# main_7.net
KiCad netlist of a schematic drawn in Altium Designer
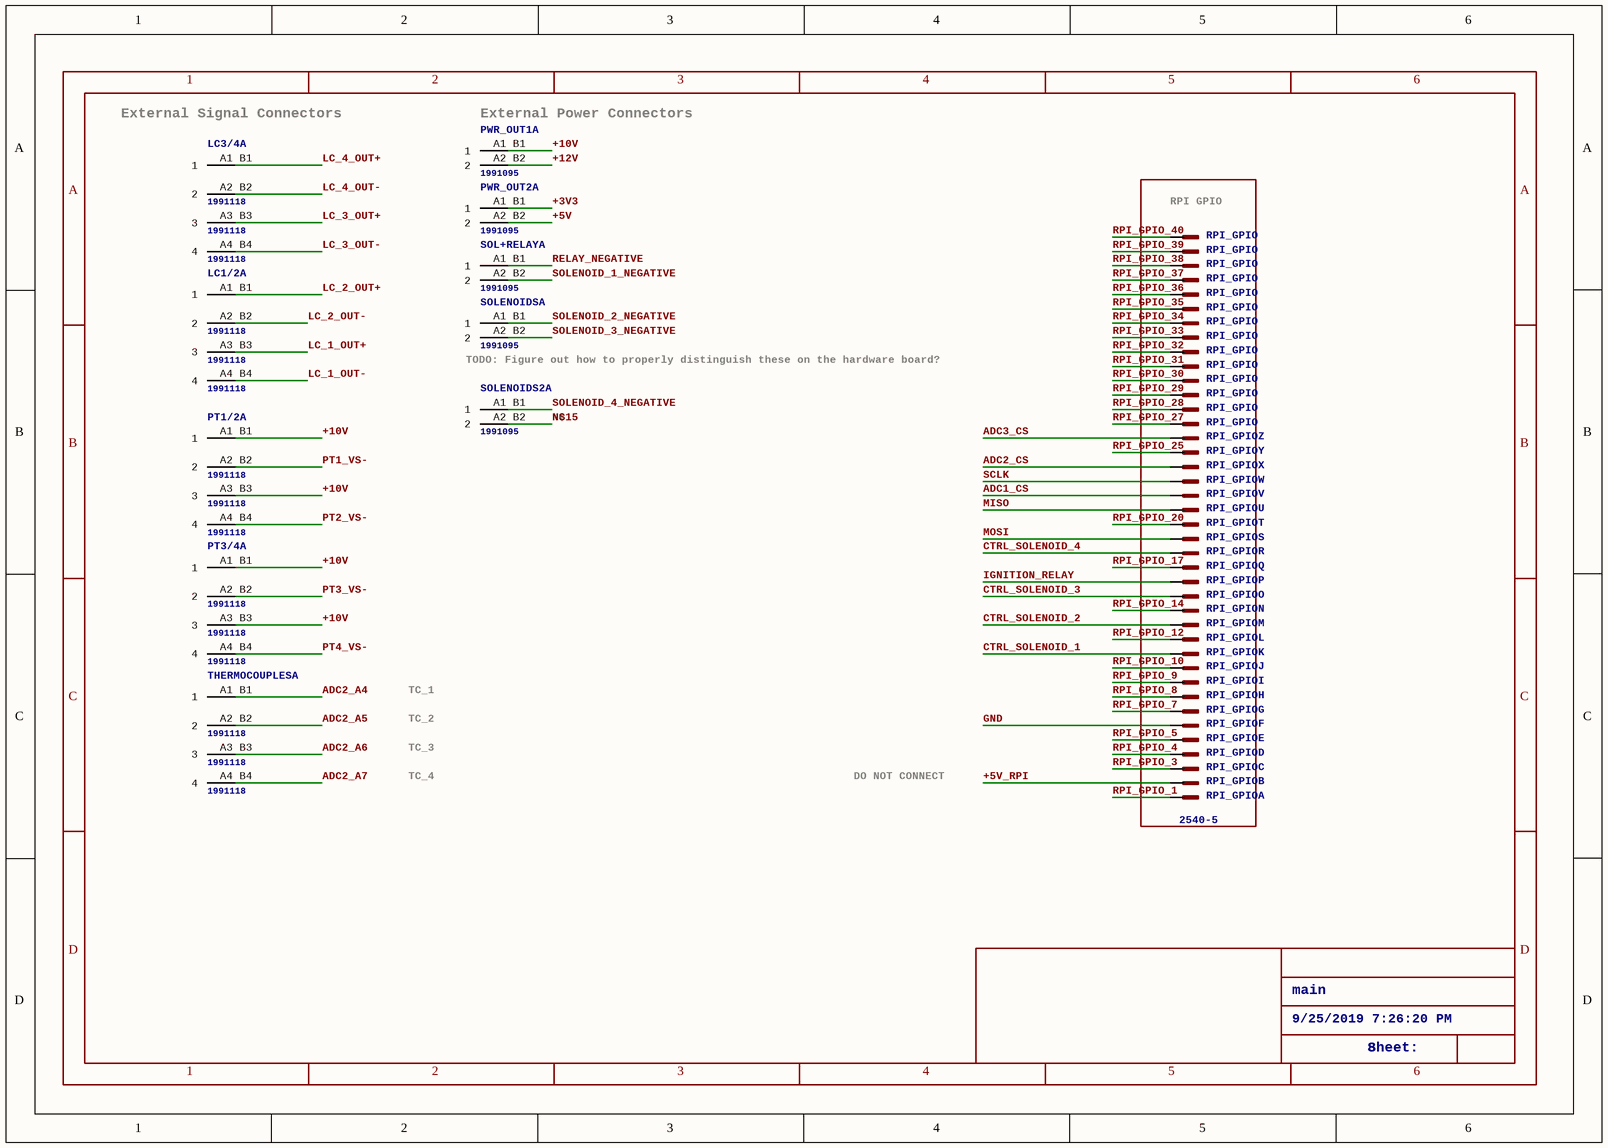
[diagram p0: main_7.SchDoc]

(export (version "E")
  (design (tool "Eeschema 10.0.6"))
  (components
    (comp (ref "LC1/2")
      (value "1991118")
      (footprint "1991118")
      (fields (field (name "LIBRARYNAME") "con-phoenix-500-extra"))
      (libsource (lib "con-phoenix-500-extra") (part "1991118"))
    )
    (comp (ref "LC3/4")
      (value "1991118")
      (footprint "1991118")
      (fields (field (name "LIBRARYNAME") "con-phoenix-500-extra"))
      (libsource (lib "con-phoenix-500-extra") (part "1991118"))
    )
    (comp (ref "PT1/2")
      (value "1991118")
      (footprint "1991118")
      (fields (field (name "LIBRARYNAME") "con-phoenix-500-extra"))
      (libsource (lib "con-phoenix-500-extra") (part "1991118"))
    )
    (comp (ref "PT3/4")
      (value "1991118")
      (footprint "1991118")
      (fields (field (name "LIBRARYNAME") "con-phoenix-500-extra"))
      (libsource (lib "con-phoenix-500-extra") (part "1991118"))
    )
    (comp (ref "PWR_OUT1")
      (value "1991095")
      (footprint "1991095")
      (fields (field (name "LIBRARYNAME") "con-phoenix-500-extra"))
      (libsource (lib "con-phoenix-500-extra") (part "1991095"))
    )
    (comp (ref "PWR_OUT2")
      (value "1991095")
      (footprint "1991095")
      (fields (field (name "LIBRARYNAME") "con-phoenix-500-extra"))
      (libsource (lib "con-phoenix-500-extra") (part "1991095"))
    )
    (comp (ref "RPI_GPIO")
      (value "2540-5")
      (footprint "PAK100/2500-5-40")
      (description "3M (TM) Pak 100 4-Wall HeaderSource: 3M")
      (libsource (lib "con-3m") (part "2540-5"))
    )
    (comp (ref "SOL+RELAY")
      (value "1991095")
      (footprint "1991095")
      (fields (field (name "LIBRARYNAME") "con-phoenix-500-extra"))
      (libsource (lib "con-phoenix-500-extra") (part "1991095"))
    )
    (comp (ref "SOLENOIDS")
      (value "1991095")
      (footprint "1991095")
      (fields (field (name "LIBRARYNAME") "con-phoenix-500-extra"))
      (libsource (lib "con-phoenix-500-extra") (part "1991095"))
    )
    (comp (ref "SOLENOIDS2")
      (value "1991095")
      (footprint "1991095")
      (fields (field (name "LIBRARYNAME") "con-phoenix-500-extra"))
      (libsource (lib "con-phoenix-500-extra") (part "1991095"))
    )
    (comp (ref "THERMOCOUPLES")
      (value "1991118")
      (footprint "1991118")
      (fields (field (name "LIBRARYNAME") "con-phoenix-500-extra"))
      (libsource (lib "con-phoenix-500-extra") (part "1991118"))
    )
  )
  (nets
    (net (code "1") (name "/+3V3") (class "Default")
      (node (ref "PWR_OUT2") (pin "A1_B1") (pinfunction "1_A1_B1") (pintype "passive"))
    )
    (net (code "2") (name "/+5V") (class "Default")
      (node (ref "PWR_OUT2") (pin "A2_B2") (pinfunction "2_A2_B2") (pintype "passive"))
    )
    (net (code "3") (name "/+5V_RPI") (class "Default")
      (node (ref "RPI_GPIO") (pin "2") (pinfunction "KL_2") (pintype "passive"))
    )
    (net (code "4") (name "/+10V") (class "Default")
      (node (ref "PT1/2") (pin "A1_B1") (pinfunction "1_A1_B1") (pintype "passive"))
      (node (ref "PT1/2") (pin "A3_B3") (pinfunction "3_A3_B3") (pintype "passive"))
      (node (ref "PT3/4") (pin "A1_B1") (pinfunction "1_A1_B1") (pintype "passive"))
      (node (ref "PT3/4") (pin "A3_B3") (pinfunction "3_A3_B3") (pintype "passive"))
      (node (ref "PWR_OUT1") (pin "A1_B1") (pinfunction "1_A1_B1") (pintype "passive"))
    )
    (net (code "5") (name "/+12V") (class "Default")
      (node (ref "PWR_OUT1") (pin "A2_B2") (pinfunction "2_A2_B2") (pintype "passive"))
    )
    (net (code "6") (name "/ADC1_CS") (class "Default")
      (node (ref "RPI_GPIO") (pin "22") (pinfunction "KL_22") (pintype "passive"))
    )
    (net (code "7") (name "/ADC2_A4") (class "Default")
      (node (ref "THERMOCOUPLES") (pin "A1_B1") (pinfunction "1_A1_B1") (pintype "passive"))
    )
    (net (code "8") (name "/ADC2_A5") (class "Default")
      (node (ref "THERMOCOUPLES") (pin "A2_B2") (pinfunction "2_A2_B2") (pintype "passive"))
    )
    (net (code "9") (name "/ADC2_A6") (class "Default")
      (node (ref "THERMOCOUPLES") (pin "A3_B3") (pinfunction "3_A3_B3") (pintype "passive"))
    )
    (net (code "10") (name "/ADC2_A7") (class "Default")
      (node (ref "THERMOCOUPLES") (pin "A4_B4") (pinfunction "4_A4_B4") (pintype "passive"))
    )
    (net (code "11") (name "/ADC2_CS") (class "Default")
      (node (ref "RPI_GPIO") (pin "24") (pinfunction "KL_24") (pintype "passive"))
    )
    (net (code "12") (name "/ADC3_CS") (class "Default")
      (node (ref "RPI_GPIO") (pin "26") (pinfunction "KL_26") (pintype "passive"))
    )
    (net (code "13") (name "/CTRL_SOLENOID_1") (class "Default")
      (node (ref "RPI_GPIO") (pin "11") (pinfunction "KL_11") (pintype "passive"))
    )
    (net (code "14") (name "/CTRL_SOLENOID_2") (class "Default")
      (node (ref "RPI_GPIO") (pin "13") (pinfunction "KL_13") (pintype "passive"))
    )
    (net (code "15") (name "/CTRL_SOLENOID_3") (class "Default")
      (node (ref "RPI_GPIO") (pin "15") (pinfunction "KL_15") (pintype "passive"))
    )
    (net (code "16") (name "/CTRL_SOLENOID_4") (class "Default")
      (node (ref "RPI_GPIO") (pin "18") (pinfunction "KL_18") (pintype "passive"))
    )
    (net (code "17") (name "/GND") (class "Default")
      (node (ref "RPI_GPIO") (pin "6") (pinfunction "KL_6") (pintype "passive"))
    )
    (net (code "18") (name "/IGNITION_RELAY") (class "Default")
      (node (ref "RPI_GPIO") (pin "16") (pinfunction "KL_16") (pintype "passive"))
    )
    (net (code "19") (name "/LC_1_OUT+") (class "Default")
      (node (ref "LC1/2") (pin "A3_B3") (pinfunction "3_A3_B3") (pintype "passive"))
    )
    (net (code "20") (name "/LC_1_OUT-") (class "Default")
      (node (ref "LC1/2") (pin "A4_B4") (pinfunction "4_A4_B4") (pintype "passive"))
    )
    (net (code "21") (name "/LC_2_OUT+") (class "Default")
      (node (ref "LC1/2") (pin "A1_B1") (pinfunction "1_A1_B1") (pintype "passive"))
    )
    (net (code "22") (name "/LC_2_OUT-") (class "Default")
      (node (ref "LC1/2") (pin "A2_B2") (pinfunction "2_A2_B2") (pintype "passive"))
    )
    (net (code "23") (name "/LC_3_OUT+") (class "Default")
      (node (ref "LC3/4") (pin "A3_B3") (pinfunction "3_A3_B3") (pintype "passive"))
    )
    (net (code "24") (name "/LC_3_OUT-") (class "Default")
      (node (ref "LC3/4") (pin "A4_B4") (pinfunction "4_A4_B4") (pintype "passive"))
    )
    (net (code "25") (name "/LC_4_OUT+") (class "Default")
      (node (ref "LC3/4") (pin "A1_B1") (pinfunction "1_A1_B1") (pintype "passive"))
    )
    (net (code "26") (name "/LC_4_OUT-") (class "Default")
      (node (ref "LC3/4") (pin "A2_B2") (pinfunction "2_A2_B2") (pintype "passive"))
    )
    (net (code "27") (name "/MISO") (class "Default")
      (node (ref "RPI_GPIO") (pin "21") (pinfunction "KL_21") (pintype "passive"))
    )
    (net (code "28") (name "/MOSI") (class "Default")
      (node (ref "RPI_GPIO") (pin "19") (pinfunction "KL_19") (pintype "passive"))
    )
    (net (code "29") (name "/N$15") (class "Default")
      (node (ref "SOLENOIDS2") (pin "A2_B2") (pinfunction "2_A2_B2") (pintype "passive"))
    )
    (net (code "30") (name "/PT1_VS-") (class "Default")
      (node (ref "PT1/2") (pin "A2_B2") (pinfunction "2_A2_B2") (pintype "passive"))
    )
    (net (code "31") (name "/PT2_VS-") (class "Default")
      (node (ref "PT1/2") (pin "A4_B4") (pinfunction "4_A4_B4") (pintype "passive"))
    )
    (net (code "32") (name "/PT3_VS-") (class "Default")
      (node (ref "PT3/4") (pin "A2_B2") (pinfunction "2_A2_B2") (pintype "passive"))
    )
    (net (code "33") (name "/PT4_VS-") (class "Default")
      (node (ref "PT3/4") (pin "A4_B4") (pinfunction "4_A4_B4") (pintype "passive"))
    )
    (net (code "34") (name "/RELAY_NEGATIVE") (class "Default")
      (node (ref "SOL+RELAY") (pin "A1_B1") (pinfunction "1_A1_B1") (pintype "passive"))
    )
    (net (code "35") (name "/RPI_GPIO_1") (class "Default")
      (node (ref "RPI_GPIO") (pin "1") (pinfunction "KL_1") (pintype "passive"))
    )
    (net (code "36") (name "/RPI_GPIO_3") (class "Default")
      (node (ref "RPI_GPIO") (pin "3") (pinfunction "KL_3") (pintype "passive"))
    )
    (net (code "37") (name "/RPI_GPIO_4") (class "Default")
      (node (ref "RPI_GPIO") (pin "4") (pinfunction "KL_4") (pintype "passive"))
    )
    (net (code "38") (name "/RPI_GPIO_5") (class "Default")
      (node (ref "RPI_GPIO") (pin "5") (pinfunction "KL_5") (pintype "passive"))
    )
    (net (code "39") (name "/RPI_GPIO_7") (class "Default")
      (node (ref "RPI_GPIO") (pin "7") (pinfunction "KL_7") (pintype "passive"))
    )
    (net (code "40") (name "/RPI_GPIO_8") (class "Default")
      (node (ref "RPI_GPIO") (pin "8") (pinfunction "KL_8") (pintype "passive"))
    )
    (net (code "41") (name "/RPI_GPIO_9") (class "Default")
      (node (ref "RPI_GPIO") (pin "9") (pinfunction "KL_9") (pintype "passive"))
    )
    (net (code "42") (name "/RPI_GPIO_10") (class "Default")
      (node (ref "RPI_GPIO") (pin "10") (pinfunction "KL_10") (pintype "passive"))
    )
    (net (code "43") (name "/RPI_GPIO_12") (class "Default")
      (node (ref "RPI_GPIO") (pin "12") (pinfunction "KL_12") (pintype "passive"))
    )
    (net (code "44") (name "/RPI_GPIO_14") (class "Default")
      (node (ref "RPI_GPIO") (pin "14") (pinfunction "KL_14") (pintype "passive"))
    )
    (net (code "45") (name "/RPI_GPIO_17") (class "Default")
      (node (ref "RPI_GPIO") (pin "17") (pinfunction "KL_17") (pintype "passive"))
    )
    (net (code "46") (name "/RPI_GPIO_20") (class "Default")
      (node (ref "RPI_GPIO") (pin "20") (pinfunction "KL_20") (pintype "passive"))
    )
    (net (code "47") (name "/RPI_GPIO_25") (class "Default")
      (node (ref "RPI_GPIO") (pin "25") (pinfunction "KL_25") (pintype "passive"))
    )
    (net (code "48") (name "/RPI_GPIO_27") (class "Default")
      (node (ref "RPI_GPIO") (pin "27") (pinfunction "KL_27") (pintype "passive"))
    )
    (net (code "49") (name "/RPI_GPIO_28") (class "Default")
      (node (ref "RPI_GPIO") (pin "28") (pinfunction "KL_28") (pintype "passive"))
    )
    (net (code "50") (name "/RPI_GPIO_29") (class "Default")
      (node (ref "RPI_GPIO") (pin "29") (pinfunction "KL_29") (pintype "passive"))
    )
    (net (code "51") (name "/RPI_GPIO_30") (class "Default")
      (node (ref "RPI_GPIO") (pin "30") (pinfunction "KL_30") (pintype "passive"))
    )
    (net (code "52") (name "/RPI_GPIO_31") (class "Default")
      (node (ref "RPI_GPIO") (pin "31") (pinfunction "KL_31") (pintype "passive"))
    )
    (net (code "53") (name "/RPI_GPIO_32") (class "Default")
      (node (ref "RPI_GPIO") (pin "32") (pinfunction "KL_32") (pintype "passive"))
    )
    (net (code "54") (name "/RPI_GPIO_33") (class "Default")
      (node (ref "RPI_GPIO") (pin "33") (pinfunction "KL_33") (pintype "passive"))
    )
    (net (code "55") (name "/RPI_GPIO_34") (class "Default")
      (node (ref "RPI_GPIO") (pin "34") (pinfunction "KL_34") (pintype "passive"))
    )
    (net (code "56") (name "/RPI_GPIO_35") (class "Default")
      (node (ref "RPI_GPIO") (pin "35") (pinfunction "KL_35") (pintype "passive"))
    )
    (net (code "57") (name "/RPI_GPIO_36") (class "Default")
      (node (ref "RPI_GPIO") (pin "36") (pinfunction "KL_36") (pintype "passive"))
    )
    (net (code "58") (name "/RPI_GPIO_37") (class "Default")
      (node (ref "RPI_GPIO") (pin "37") (pinfunction "KL_37") (pintype "passive"))
    )
    (net (code "59") (name "/RPI_GPIO_38") (class "Default")
      (node (ref "RPI_GPIO") (pin "38") (pinfunction "KL_38") (pintype "passive"))
    )
    (net (code "60") (name "/RPI_GPIO_39") (class "Default")
      (node (ref "RPI_GPIO") (pin "39") (pinfunction "KL_39") (pintype "passive"))
    )
    (net (code "61") (name "/RPI_GPIO_40") (class "Default")
      (node (ref "RPI_GPIO") (pin "40") (pinfunction "KL_40") (pintype "passive"))
    )
    (net (code "62") (name "/SCLK") (class "Default")
      (node (ref "RPI_GPIO") (pin "23") (pinfunction "KL_23") (pintype "passive"))
    )
    (net (code "63") (name "/SOLENOID_1_NEGATIVE") (class "Default")
      (node (ref "SOL+RELAY") (pin "A2_B2") (pinfunction "2_A2_B2") (pintype "passive"))
    )
    (net (code "64") (name "/SOLENOID_2_NEGATIVE") (class "Default")
      (node (ref "SOLENOIDS") (pin "A1_B1") (pinfunction "1_A1_B1") (pintype "passive"))
    )
    (net (code "65") (name "/SOLENOID_3_NEGATIVE") (class "Default")
      (node (ref "SOLENOIDS") (pin "A2_B2") (pinfunction "2_A2_B2") (pintype "passive"))
    )
    (net (code "66") (name "/SOLENOID_4_NEGATIVE") (class "Default")
      (node (ref "SOLENOIDS2") (pin "A1_B1") (pinfunction "1_A1_B1") (pintype "passive"))
    )
  )
)
